# Integrator.net
KiCad netlist of a schematic drawn in Altium Designer
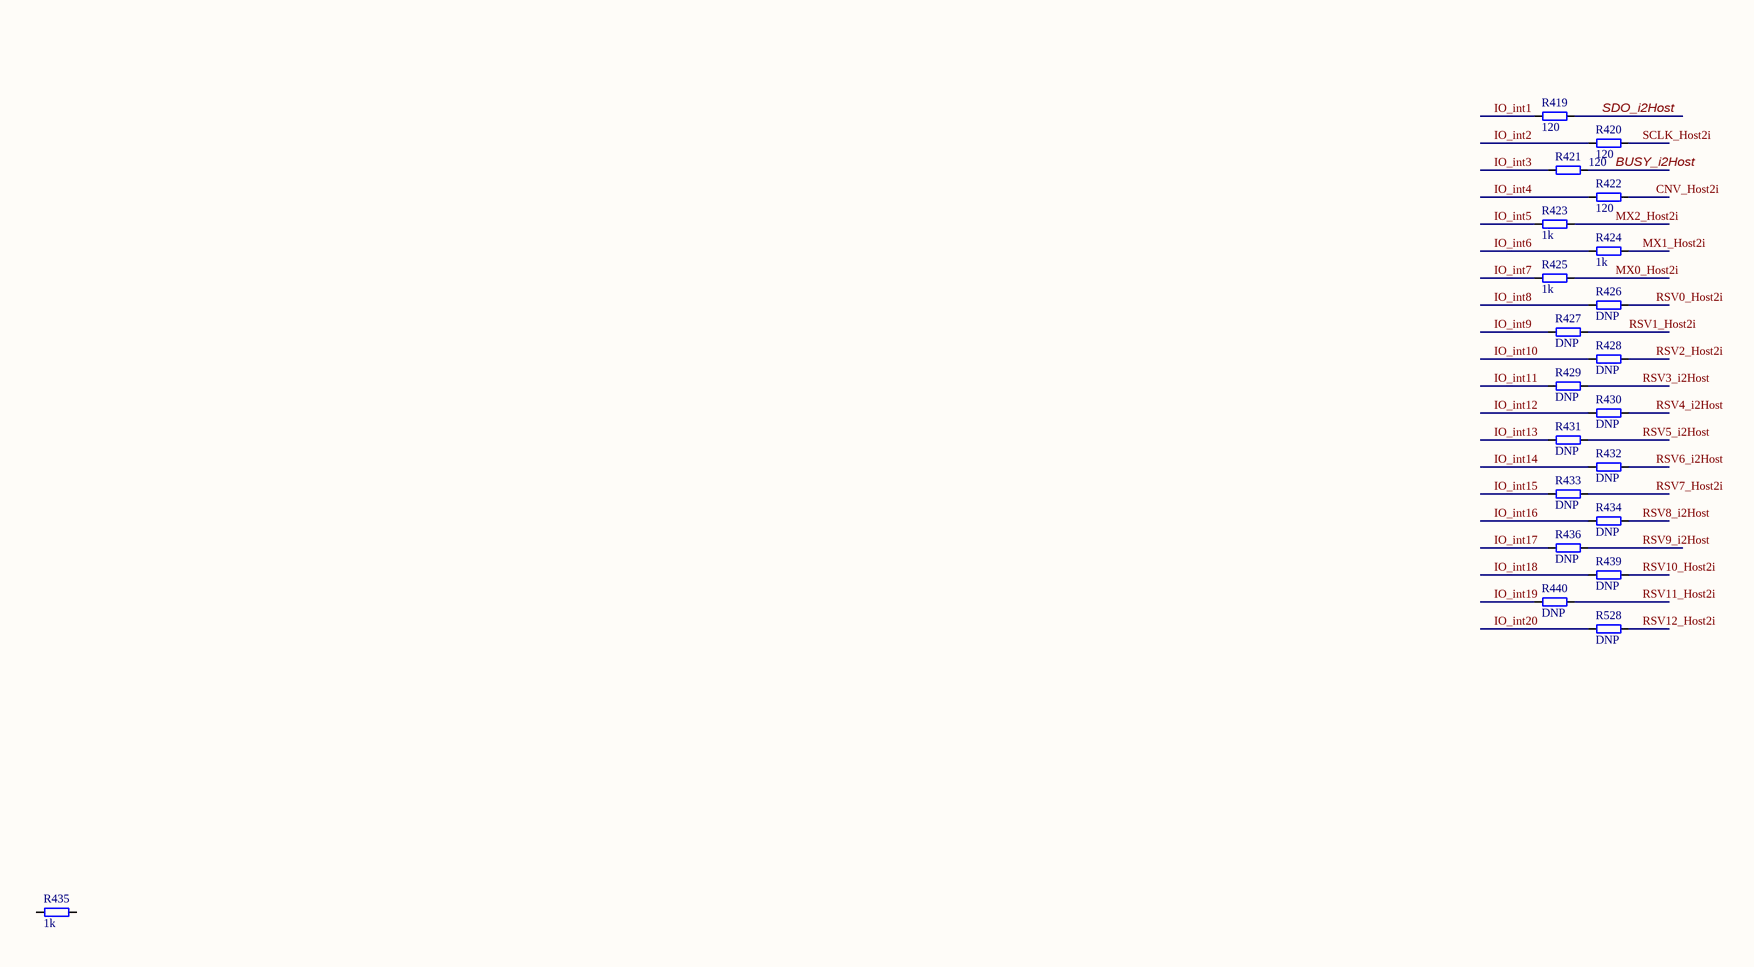
[diagram p0: Integrator.SchDoc, left]
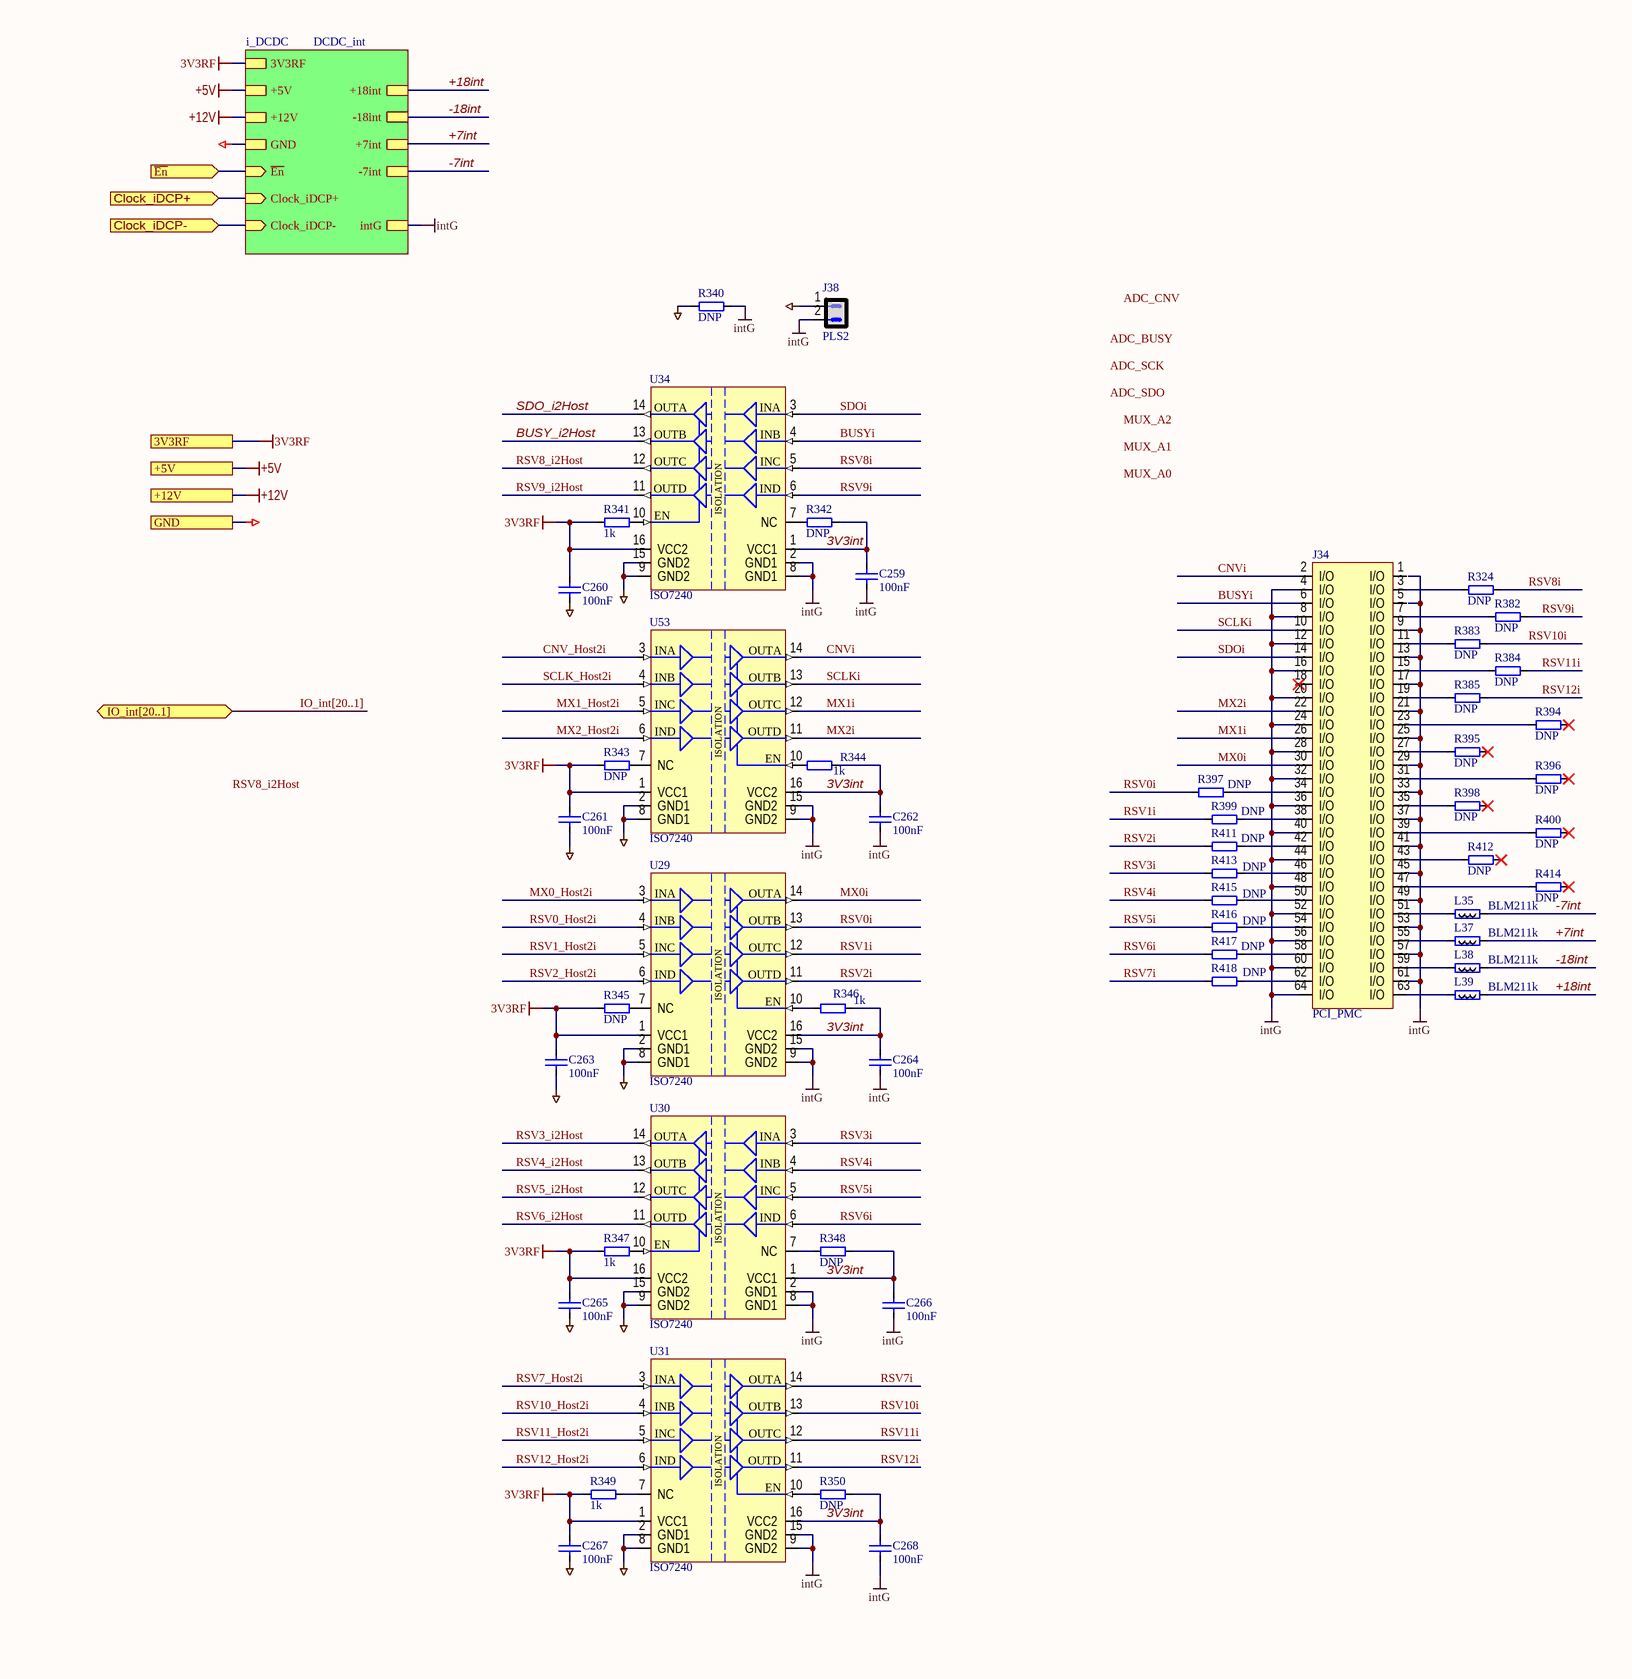
[diagram p1: Integrator.SchDoc, right]

(export (version "E")
  (design (tool "Eeschema 10.0.6"))
  (components
    (comp (ref "C259")
      (value "100nF")
      (footprint "SMD0805CAP")
      (description "Чип конденсатор 0805")
      (fields (field (name "VOLTAGE") "25V") (field (name "TOLERANCE") "20%"))
      (libsource (lib "DDSintLib") (part "C0805"))
    )
    (comp (ref "C260")
      (value "100nF")
      (footprint "SMD0805CAP")
      (description "Чип конденсатор 0805")
      (fields (field (name "VOLTAGE") "25V") (field (name "TOLERANCE") "20%"))
      (libsource (lib "DDSintLib") (part "C0805"))
    )
    (comp (ref "C261")
      (value "100nF")
      (footprint "SMD0805CAP")
      (description "Чип конденсатор 0805")
      (fields (field (name "VOLTAGE") "25V") (field (name "TOLERANCE") "20%"))
      (libsource (lib "DDSintLib") (part "C0805"))
    )
    (comp (ref "C262")
      (value "100nF")
      (footprint "SMD0805CAP")
      (description "Чип конденсатор 0805")
      (fields (field (name "VOLTAGE") "25V") (field (name "TOLERANCE") "20%"))
      (libsource (lib "DDSintLib") (part "C0805"))
    )
    (comp (ref "C263")
      (value "100nF")
      (footprint "SMD0805CAP")
      (description "Чип конденсатор 0805")
      (fields (field (name "VOLTAGE") "25V") (field (name "TOLERANCE") "20%"))
      (libsource (lib "DDSintLib") (part "C0805"))
    )
    (comp (ref "C264")
      (value "100nF")
      (footprint "SMD0805CAP")
      (description "Чип конденсатор 0805")
      (fields (field (name "VOLTAGE") "25V") (field (name "TOLERANCE") "20%"))
      (libsource (lib "DDSintLib") (part "C0805"))
    )
    (comp (ref "C265")
      (value "100nF")
      (footprint "SMD0805CAP")
      (description "Чип конденсатор 0805")
      (fields (field (name "VOLTAGE") "25V") (field (name "TOLERANCE") "20%"))
      (libsource (lib "DDSintLib") (part "C0805"))
    )
    (comp (ref "C266")
      (value "100nF")
      (footprint "SMD0805CAP")
      (description "Чип конденсатор 0805")
      (fields (field (name "VOLTAGE") "25V") (field (name "TOLERANCE") "20%"))
      (libsource (lib "DDSintLib") (part "C0805"))
    )
    (comp (ref "C267")
      (value "100nF")
      (footprint "SMD0805CAP")
      (description "Чип конденсатор 0805")
      (fields (field (name "VOLTAGE") "25V") (field (name "TOLERANCE") "20%"))
      (libsource (lib "DDSintLib") (part "C0805"))
    )
    (comp (ref "C268")
      (value "100nF")
      (footprint "SMD0805CAP")
      (description "Чип конденсатор 0805")
      (fields (field (name "VOLTAGE") "25V") (field (name "TOLERANCE") "20%"))
      (libsource (lib "DDSintLib") (part "C0805"))
    )
    (comp (ref "J34")
      (value "PCI_PMC")
      (footprint "TYCO_120521-1")
      (description "PCI Mezzanine Connector; IEEE 1386 MainBoard")
      (libsource (lib "DDSintLib") (part "PCI_PMC_M"))
    )
    (comp (ref "J38") (value "PLS2") (footprint "PLS2") (libsource (lib "DDSintLib") (part "PLS2")))
    (comp (ref "L35")
      (value "BLM211k")
      (footprint "RESC2012X50N")
      (description "SMD Ferrite bead 0805")
      (libsource (lib "DDSintLib") (part "BLM21"))
    )
    (comp (ref "L37")
      (value "BLM211k")
      (footprint "RESC2012X50N")
      (description "SMD Ferrite bead 0805")
      (libsource (lib "DDSintLib") (part "BLM21"))
    )
    (comp (ref "L38")
      (value "BLM211k")
      (footprint "RESC2012X50N")
      (description "SMD Ferrite bead 0805")
      (libsource (lib "DDSintLib") (part "BLM21"))
    )
    (comp (ref "L39")
      (value "BLM211k")
      (footprint "RESC2012X50N")
      (description "SMD Ferrite bead 0805")
      (libsource (lib "DDSintLib") (part "BLM21"))
    )
    (comp (ref "R324")
      (value "DNP")
      (footprint "SMD0805RES")
      (description "Чип резистор 0805")
      (fields (field (name "TOLERANCE") "1%"))
      (libsource (lib "DDSintLib") (part "R0805"))
    )
    (comp (ref "R340")
      (value "DNP")
      (footprint "SMD0805RES")
      (description "Чип резистор 0805")
      (fields (field (name "TOLERANCE") "1%"))
      (libsource (lib "DDSintLib") (part "R0805"))
    )
    (comp (ref "R341")
      (value "1k")
      (footprint "SMD0805RES")
      (description "Чип резистор 0805")
      (fields (field (name "TOLERANCE") "1%"))
      (libsource (lib "DDSintLib") (part "R0805"))
    )
    (comp (ref "R342")
      (value "DNP")
      (footprint "SMD0805RES")
      (description "Чип резистор 0805")
      (fields (field (name "TOLERANCE") "1%"))
      (libsource (lib "DDSintLib") (part "R0805"))
    )
    (comp (ref "R343")
      (value "DNP")
      (footprint "SMD0805RES")
      (description "Чип резистор 0805")
      (fields (field (name "TOLERANCE") "1%"))
      (libsource (lib "DDSintLib") (part "R0805"))
    )
    (comp (ref "R344")
      (value "1k")
      (footprint "SMD0805RES")
      (description "Чип резистор 0805")
      (fields (field (name "TOLERANCE") "1%"))
      (libsource (lib "DDSintLib") (part "R0805"))
    )
    (comp (ref "R345")
      (value "DNP")
      (footprint "SMD0805RES")
      (description "Чип резистор 0805")
      (fields (field (name "TOLERANCE") "1%"))
      (libsource (lib "DDSintLib") (part "R0805"))
    )
    (comp (ref "R346")
      (value "1k")
      (footprint "SMD0805RES")
      (description "Чип резистор 0805")
      (fields (field (name "TOLERANCE") "1%"))
      (libsource (lib "DDSintLib") (part "R0805"))
    )
    (comp (ref "R347")
      (value "1k")
      (footprint "SMD0805RES")
      (description "Чип резистор 0805")
      (fields (field (name "TOLERANCE") "1%"))
      (libsource (lib "DDSintLib") (part "R0805"))
    )
    (comp (ref "R348")
      (value "DNP")
      (footprint "SMD0805RES")
      (description "Чип резистор 0805")
      (fields (field (name "TOLERANCE") "1%"))
      (libsource (lib "DDSintLib") (part "R0805"))
    )
    (comp (ref "R349")
      (value "1k")
      (footprint "SMD0805RES")
      (description "Чип резистор 0805")
      (fields (field (name "TOLERANCE") "1%"))
      (libsource (lib "DDSintLib") (part "R0805"))
    )
    (comp (ref "R350")
      (value "DNP")
      (footprint "SMD0805RES")
      (description "Чип резистор 0805")
      (fields (field (name "TOLERANCE") "1%"))
      (libsource (lib "DDSintLib") (part "R0805"))
    )
    (comp (ref "R382")
      (value "DNP")
      (footprint "SMD0805RES")
      (description "Чип резистор 0805")
      (fields (field (name "TOLERANCE") "1%"))
      (libsource (lib "DDSintLib") (part "R0805"))
    )
    (comp (ref "R383")
      (value "DNP")
      (footprint "SMD0805RES")
      (description "Чип резистор 0805")
      (fields (field (name "TOLERANCE") "1%"))
      (libsource (lib "DDSintLib") (part "R0805"))
    )
    (comp (ref "R384")
      (value "DNP")
      (footprint "SMD0805RES")
      (description "Чип резистор 0805")
      (fields (field (name "TOLERANCE") "1%"))
      (libsource (lib "DDSintLib") (part "R0805"))
    )
    (comp (ref "R385")
      (value "DNP")
      (footprint "SMD0805RES")
      (description "Чип резистор 0805")
      (fields (field (name "TOLERANCE") "1%"))
      (libsource (lib "DDSintLib") (part "R0805"))
    )
    (comp (ref "R394")
      (value "DNP")
      (footprint "SMD0805RES")
      (description "Чип резистор 0805")
      (fields (field (name "TOLERANCE") "1%"))
      (libsource (lib "DDSintLib") (part "R0805"))
    )
    (comp (ref "R395")
      (value "DNP")
      (footprint "SMD0805RES")
      (description "Чип резистор 0805")
      (fields (field (name "TOLERANCE") "1%"))
      (libsource (lib "DDSintLib") (part "R0805"))
    )
    (comp (ref "R396")
      (value "DNP")
      (footprint "SMD0805RES")
      (description "Чип резистор 0805")
      (fields (field (name "TOLERANCE") "1%"))
      (libsource (lib "DDSintLib") (part "R0805"))
    )
    (comp (ref "R397")
      (value "DNP")
      (footprint "SMD0805RES")
      (description "Чип резистор 0805")
      (fields (field (name "TOLERANCE") "1%"))
      (libsource (lib "DDSintLib") (part "R0805"))
    )
    (comp (ref "R398")
      (value "DNP")
      (footprint "SMD0805RES")
      (description "Чип резистор 0805")
      (fields (field (name "TOLERANCE") "1%"))
      (libsource (lib "DDSintLib") (part "R0805"))
    )
    (comp (ref "R399")
      (value "DNP")
      (footprint "SMD0805RES")
      (description "Чип резистор 0805")
      (fields (field (name "TOLERANCE") "1%"))
      (libsource (lib "DDSintLib") (part "R0805"))
    )
    (comp (ref "R400")
      (value "DNP")
      (footprint "SMD0805RES")
      (description "Чип резистор 0805")
      (fields (field (name "TOLERANCE") "1%"))
      (libsource (lib "DDSintLib") (part "R0805"))
    )
    (comp (ref "R411")
      (value "DNP")
      (footprint "SMD0805RES")
      (description "Чип резистор 0805")
      (fields (field (name "TOLERANCE") "1%"))
      (libsource (lib "DDSintLib") (part "R0805"))
    )
    (comp (ref "R412")
      (value "DNP")
      (footprint "SMD0805RES")
      (description "Чип резистор 0805")
      (fields (field (name "TOLERANCE") "1%"))
      (libsource (lib "DDSintLib") (part "R0805"))
    )
    (comp (ref "R413")
      (value "DNP")
      (footprint "SMD0805RES")
      (description "Чип резистор 0805")
      (fields (field (name "TOLERANCE") "1%"))
      (libsource (lib "DDSintLib") (part "R0805"))
    )
    (comp (ref "R414")
      (value "DNP")
      (footprint "SMD0805RES")
      (description "Чип резистор 0805")
      (fields (field (name "TOLERANCE") "1%"))
      (libsource (lib "DDSintLib") (part "R0805"))
    )
    (comp (ref "R415")
      (value "DNP")
      (footprint "SMD0805RES")
      (description "Чип резистор 0805")
      (fields (field (name "TOLERANCE") "1%"))
      (libsource (lib "DDSintLib") (part "R0805"))
    )
    (comp (ref "R416")
      (value "DNP")
      (footprint "SMD0805RES")
      (description "Чип резистор 0805")
      (fields (field (name "TOLERANCE") "1%"))
      (libsource (lib "DDSintLib") (part "R0805"))
    )
    (comp (ref "R417")
      (value "DNP")
      (footprint "SMD0805RES")
      (description "Чип резистор 0805")
      (fields (field (name "TOLERANCE") "1%"))
      (libsource (lib "DDSintLib") (part "R0805"))
    )
    (comp (ref "R418")
      (value "DNP")
      (footprint "SMD0805RES")
      (description "Чип резистор 0805")
      (fields (field (name "TOLERANCE") "1%"))
      (libsource (lib "DDSintLib") (part "R0805"))
    )
    (comp (ref "R419")
      (value "120")
      (footprint "SMD0805RES")
      (description "Чип резистор 0805")
      (fields (field (name "TOLERANCE") "1%"))
      (libsource (lib "DDSintLib") (part "R0805"))
    )
    (comp (ref "R420")
      (value "120")
      (footprint "SMD0805RES")
      (description "Чип резистор 0805")
      (fields (field (name "TOLERANCE") "1%"))
      (libsource (lib "DDSintLib") (part "R0805"))
    )
    (comp (ref "R421")
      (value "120")
      (footprint "SMD0805RES")
      (description "Чип резистор 0805")
      (fields (field (name "TOLERANCE") "1%"))
      (libsource (lib "DDSintLib") (part "R0805"))
    )
    (comp (ref "R422")
      (value "120")
      (footprint "SMD0805RES")
      (description "Чип резистор 0805")
      (fields (field (name "TOLERANCE") "1%"))
      (libsource (lib "DDSintLib") (part "R0805"))
    )
    (comp (ref "R423")
      (value "1k")
      (footprint "SMD0805RES")
      (description "Чип резистор 0805")
      (fields (field (name "TOLERANCE") "1%"))
      (libsource (lib "DDSintLib") (part "R0805"))
    )
    (comp (ref "R424")
      (value "1k")
      (footprint "SMD0805RES")
      (description "Чип резистор 0805")
      (fields (field (name "TOLERANCE") "1%"))
      (libsource (lib "DDSintLib") (part "R0805"))
    )
    (comp (ref "R425")
      (value "1k")
      (footprint "SMD0805RES")
      (description "Чип резистор 0805")
      (fields (field (name "TOLERANCE") "1%"))
      (libsource (lib "DDSintLib") (part "R0805"))
    )
    (comp (ref "R426")
      (value "DNP")
      (footprint "SMD0805RES")
      (description "Чип резистор 0805")
      (fields (field (name "TOLERANCE") "1%"))
      (libsource (lib "DDSintLib") (part "R0805"))
    )
    (comp (ref "R427")
      (value "DNP")
      (footprint "SMD0805RES")
      (description "Чип резистор 0805")
      (fields (field (name "TOLERANCE") "1%"))
      (libsource (lib "DDSintLib") (part "R0805"))
    )
    (comp (ref "R428")
      (value "DNP")
      (footprint "SMD0805RES")
      (description "Чип резистор 0805")
      (fields (field (name "TOLERANCE") "1%"))
      (libsource (lib "DDSintLib") (part "R0805"))
    )
    (comp (ref "R429")
      (value "DNP")
      (footprint "SMD0805RES")
      (description "Чип резистор 0805")
      (fields (field (name "TOLERANCE") "1%"))
      (libsource (lib "DDSintLib") (part "R0805"))
    )
    (comp (ref "R430")
      (value "DNP")
      (footprint "SMD0805RES")
      (description "Чип резистор 0805")
      (fields (field (name "TOLERANCE") "1%"))
      (libsource (lib "DDSintLib") (part "R0805"))
    )
    (comp (ref "R431")
      (value "DNP")
      (footprint "SMD0805RES")
      (description "Чип резистор 0805")
      (fields (field (name "TOLERANCE") "1%"))
      (libsource (lib "DDSintLib") (part "R0805"))
    )
    (comp (ref "R432")
      (value "DNP")
      (footprint "SMD0805RES")
      (description "Чип резистор 0805")
      (fields (field (name "TOLERANCE") "1%"))
      (libsource (lib "DDSintLib") (part "R0805"))
    )
    (comp (ref "R433")
      (value "DNP")
      (footprint "SMD0805RES")
      (description "Чип резистор 0805")
      (fields (field (name "TOLERANCE") "1%"))
      (libsource (lib "DDSintLib") (part "R0805"))
    )
    (comp (ref "R434")
      (value "DNP")
      (footprint "SMD0805RES")
      (description "Чип резистор 0805")
      (fields (field (name "TOLERANCE") "1%"))
      (libsource (lib "DDSintLib") (part "R0805"))
    )
    (comp (ref "R435")
      (value "1k")
      (footprint "SMD0805RES")
      (description "Чип резистор 0805")
      (fields (field (name "TOLERANCE") "1%"))
      (libsource (lib "DDSintLib") (part "R0805"))
    )
    (comp (ref "R436")
      (value "DNP")
      (footprint "SMD0805RES")
      (description "Чип резистор 0805")
      (fields (field (name "TOLERANCE") "1%"))
      (libsource (lib "DDSintLib") (part "R0805"))
    )
    (comp (ref "R439")
      (value "DNP")
      (footprint "SMD0805RES")
      (description "Чип резистор 0805")
      (fields (field (name "TOLERANCE") "1%"))
      (libsource (lib "DDSintLib") (part "R0805"))
    )
    (comp (ref "R440")
      (value "DNP")
      (footprint "SMD0805RES")
      (description "Чип резистор 0805")
      (fields (field (name "TOLERANCE") "1%"))
      (libsource (lib "DDSintLib") (part "R0805"))
    )
    (comp (ref "R528")
      (value "DNP")
      (footprint "SMD0805RES")
      (description "Чип резистор 0805")
      (fields (field (name "TOLERANCE") "1%"))
      (libsource (lib "DDSintLib") (part "R0805"))
    )
    (comp (ref "U29")
      (value "ISO7240")
      (footprint "SOIC127P1030X265-16N")
      (description "Двунаправленный буфер")
      (fields (field (name "VOLTAGE") "3V3 or 5V"))
      (libsource (lib "DDSintLib") (part "ISO7240M"))
    )
    (comp (ref "U30")
      (value "ISO7240")
      (footprint "SOIC127P1030X265-16N")
      (description "Двунаправленный буфер")
      (fields (field (name "VOLTAGE") "3V3 or 5V"))
      (libsource (lib "DDSintLib") (part "ISO7240M"))
    )
    (comp (ref "U31")
      (value "ISO7240")
      (footprint "SOIC127P1030X265-16N")
      (description "Двунаправленный буфер")
      (fields (field (name "VOLTAGE") "3V3 or 5V"))
      (libsource (lib "DDSintLib") (part "ISO7240M"))
    )
    (comp (ref "U34")
      (value "ISO7240")
      (footprint "SOIC127P1030X265-16N")
      (description "Двунаправленный буфер")
      (fields (field (name "VOLTAGE") "3V3 or 5V"))
      (libsource (lib "DDSintLib") (part "ISO7240M"))
    )
    (comp (ref "U53")
      (value "ISO7240")
      (footprint "SOIC127P1030X265-16N")
      (description "Двунаправленный буфер")
      (fields (field (name "VOLTAGE") "3V3 or 5V"))
      (libsource (lib "DDSintLib") (part "ISO7240M"))
    )
  )
  (nets
    (net (code "3") (name "/+7int") (class "Default")
      (node (ref "L37") (pin "2") (pinfunction "2_2") (pintype "passive"))
    )
    (net (code "4") (name "/+18int") (class "Default")
      (node (ref "L39") (pin "2") (pinfunction "2_2") (pintype "passive"))
    )
    (net (code "5") (name "/-7int") (class "Default")
      (node (ref "L35") (pin "2") (pinfunction "2_2") (pintype "passive"))
    )
    (net (code "6") (name "/-18int") (class "Default")
      (node (ref "L38") (pin "2") (pinfunction "2_2") (pintype "passive"))
    )
    (net (code "7") (name "/3V3int") (class "Default")
      (node (ref "C259") (pin "2") (pinfunction "2_2") (pintype "passive"))
      (node (ref "C262") (pin "2") (pinfunction "2_2") (pintype "passive"))
      (node (ref "C264") (pin "2") (pinfunction "2_2") (pintype "passive"))
      (node (ref "C266") (pin "2") (pinfunction "2_2") (pintype "passive"))
      (node (ref "C268") (pin "2") (pinfunction "2_2") (pintype "passive"))
      (node (ref "R342") (pin "2") (pinfunction "2_2") (pintype "passive"))
      (node (ref "R344") (pin "2") (pinfunction "2_2") (pintype "passive"))
      (node (ref "R346") (pin "2") (pinfunction "2_2") (pintype "passive"))
      (node (ref "R348") (pin "2") (pinfunction "2_2") (pintype "passive"))
      (node (ref "R350") (pin "2") (pinfunction "2_2") (pintype "passive"))
      (node (ref "U29") (pin "16") (pinfunction "VCC2_16") (pintype "power_in"))
      (node (ref "U30") (pin "1") (pinfunction "VCC1_1") (pintype "power_in"))
      (node (ref "U31") (pin "16") (pinfunction "VCC2_16") (pintype "power_in"))
      (node (ref "U34") (pin "1") (pinfunction "VCC1_1") (pintype "power_in"))
      (node (ref "U53") (pin "16") (pinfunction "VCC2_16") (pintype "power_in"))
    )
    (net (code "12") (name "/BUSY_i2Host") (class "Default")
      (node (ref "R421") (pin "2") (pinfunction "2_2") (pintype "passive"))
      (node (ref "U34") (pin "13") (pinfunction "OUTB_13") (pintype "output"))
    )
    (net (code "13") (name "/BUSYi") (class "Default")
      (node (ref "J34") (pin "6") (pinfunction "I/O_6") (pintype "bidirectional"))
      (node (ref "U34") (pin "4") (pinfunction "INB_4") (pintype "input"))
    )
    (net (code "14") (name "/CNV_Host2i") (class "Default")
      (node (ref "R422") (pin "2") (pinfunction "2_2") (pintype "passive"))
      (node (ref "U53") (pin "3") (pinfunction "INA_3") (pintype "input"))
    )
    (net (code "15") (name "/CNVi") (class "Default")
      (node (ref "J34") (pin "2") (pinfunction "I/O_2") (pintype "bidirectional"))
      (node (ref "U53") (pin "14") (pinfunction "OUTA_14") (pintype "output"))
    )
    (net (code "19") (name "/IO_int1") (class "Default")
      (node (ref "R419") (pin "1") (pinfunction "1_1") (pintype "passive"))
    )
    (net (code "20") (name "/IO_int2") (class "Default")
      (node (ref "R420") (pin "1") (pinfunction "1_1") (pintype "passive"))
    )
    (net (code "21") (name "/IO_int3") (class "Default")
      (node (ref "R421") (pin "1") (pinfunction "1_1") (pintype "passive"))
    )
    (net (code "22") (name "/IO_int4") (class "Default")
      (node (ref "R422") (pin "1") (pinfunction "1_1") (pintype "passive"))
    )
    (net (code "23") (name "/IO_int5") (class "Default")
      (node (ref "R423") (pin "1") (pinfunction "1_1") (pintype "passive"))
    )
    (net (code "24") (name "/IO_int6") (class "Default")
      (node (ref "R424") (pin "1") (pinfunction "1_1") (pintype "passive"))
    )
    (net (code "25") (name "/IO_int7") (class "Default")
      (node (ref "R425") (pin "1") (pinfunction "1_1") (pintype "passive"))
    )
    (net (code "26") (name "/IO_int8") (class "Default")
      (node (ref "R426") (pin "1") (pinfunction "1_1") (pintype "passive"))
    )
    (net (code "27") (name "/IO_int9") (class "Default")
      (node (ref "R427") (pin "1") (pinfunction "1_1") (pintype "passive"))
    )
    (net (code "28") (name "/IO_int10") (class "Default")
      (node (ref "R428") (pin "1") (pinfunction "1_1") (pintype "passive"))
    )
    (net (code "29") (name "/IO_int11") (class "Default")
      (node (ref "R429") (pin "1") (pinfunction "1_1") (pintype "passive"))
    )
    (net (code "30") (name "/IO_int12") (class "Default")
      (node (ref "R430") (pin "1") (pinfunction "1_1") (pintype "passive"))
    )
    (net (code "31") (name "/IO_int13") (class "Default")
      (node (ref "R431") (pin "1") (pinfunction "1_1") (pintype "passive"))
    )
    (net (code "32") (name "/IO_int14") (class "Default")
      (node (ref "R432") (pin "1") (pinfunction "1_1") (pintype "passive"))
    )
    (net (code "33") (name "/IO_int15") (class "Default")
      (node (ref "R433") (pin "1") (pinfunction "1_1") (pintype "passive"))
    )
    (net (code "34") (name "/IO_int16") (class "Default")
      (node (ref "R434") (pin "1") (pinfunction "1_1") (pintype "passive"))
    )
    (net (code "35") (name "/IO_int17") (class "Default")
      (node (ref "R436") (pin "1") (pinfunction "1_1") (pintype "passive"))
    )
    (net (code "36") (name "/IO_int18") (class "Default")
      (node (ref "R439") (pin "1") (pinfunction "1_1") (pintype "passive"))
    )
    (net (code "37") (name "/IO_int19") (class "Default")
      (node (ref "R440") (pin "1") (pinfunction "1_1") (pintype "passive"))
    )
    (net (code "38") (name "/IO_int20") (class "Default")
      (node (ref "R528") (pin "1") (pinfunction "1_1") (pintype "passive"))
    )
    (net (code "43") (name "/MX0_Host2i") (class "Default")
      (node (ref "R425") (pin "2") (pinfunction "2_2") (pintype "passive"))
      (node (ref "U29") (pin "3") (pinfunction "INA_3") (pintype "input"))
    )
    (net (code "44") (name "/MX0i") (class "Default")
      (node (ref "J34") (pin "30") (pinfunction "I/O_30") (pintype "bidirectional"))
      (node (ref "U29") (pin "14") (pinfunction "OUTA_14") (pintype "output"))
    )
    (net (code "45") (name "/MX1_Host2i") (class "Default")
      (node (ref "R424") (pin "2") (pinfunction "2_2") (pintype "passive"))
      (node (ref "U53") (pin "5") (pinfunction "INC_5") (pintype "input"))
    )
    (net (code "46") (name "/MX1i") (class "Default")
      (node (ref "J34") (pin "26") (pinfunction "I/O_26") (pintype "bidirectional"))
      (node (ref "U53") (pin "12") (pinfunction "OUTC_12") (pintype "output"))
    )
    (net (code "47") (name "/MX2_Host2i") (class "Default")
      (node (ref "R423") (pin "2") (pinfunction "2_2") (pintype "passive"))
      (node (ref "U53") (pin "6") (pinfunction "IND_6") (pintype "input"))
    )
    (net (code "48") (name "/MX2i") (class "Default")
      (node (ref "J34") (pin "22") (pinfunction "I/O_22") (pintype "bidirectional"))
      (node (ref "U53") (pin "11") (pinfunction "OUTD_11") (pintype "output"))
    )
    (net (code "49") (name "/RSV0_Host2i") (class "Default")
      (node (ref "R426") (pin "2") (pinfunction "2_2") (pintype "passive"))
      (node (ref "U29") (pin "4") (pinfunction "INB_4") (pintype "input"))
    )
    (net (code "50") (name "/RSV0i") (class "Default")
      (node (ref "R397") (pin "1") (pinfunction "1_1") (pintype "passive"))
      (node (ref "U29") (pin "13") (pinfunction "OUTB_13") (pintype "output"))
    )
    (net (code "51") (name "/RSV1_Host2i") (class "Default")
      (node (ref "R427") (pin "2") (pinfunction "2_2") (pintype "passive"))
      (node (ref "U29") (pin "5") (pinfunction "INC_5") (pintype "input"))
    )
    (net (code "52") (name "/RSV1i") (class "Default")
      (node (ref "R399") (pin "1") (pinfunction "1_1") (pintype "passive"))
      (node (ref "U29") (pin "12") (pinfunction "OUTC_12") (pintype "output"))
    )
    (net (code "53") (name "/RSV2_Host2i") (class "Default")
      (node (ref "R428") (pin "2") (pinfunction "2_2") (pintype "passive"))
      (node (ref "U29") (pin "6") (pinfunction "IND_6") (pintype "input"))
    )
    (net (code "54") (name "/RSV2i") (class "Default")
      (node (ref "R411") (pin "1") (pinfunction "1_1") (pintype "passive"))
      (node (ref "U29") (pin "11") (pinfunction "OUTD_11") (pintype "output"))
    )
    (net (code "55") (name "/RSV3_i2Host") (class "Default")
      (node (ref "R429") (pin "2") (pinfunction "2_2") (pintype "passive"))
      (node (ref "U30") (pin "14") (pinfunction "OUTA_14") (pintype "output"))
    )
    (net (code "56") (name "/RSV3i") (class "Default")
      (node (ref "R413") (pin "1") (pinfunction "1_1") (pintype "passive"))
      (node (ref "U30") (pin "3") (pinfunction "INA_3") (pintype "input"))
    )
    (net (code "57") (name "/RSV4_i2Host") (class "Default")
      (node (ref "R430") (pin "2") (pinfunction "2_2") (pintype "passive"))
      (node (ref "U30") (pin "13") (pinfunction "OUTB_13") (pintype "output"))
    )
    (net (code "58") (name "/RSV4i") (class "Default")
      (node (ref "R415") (pin "1") (pinfunction "1_1") (pintype "passive"))
      (node (ref "U30") (pin "4") (pinfunction "INB_4") (pintype "input"))
    )
    (net (code "59") (name "/RSV5_i2Host") (class "Default")
      (node (ref "R431") (pin "2") (pinfunction "2_2") (pintype "passive"))
      (node (ref "U30") (pin "12") (pinfunction "OUTC_12") (pintype "output"))
    )
    (net (code "60") (name "/RSV5i") (class "Default")
      (node (ref "R416") (pin "1") (pinfunction "1_1") (pintype "passive"))
      (node (ref "U30") (pin "5") (pinfunction "INC_5") (pintype "input"))
    )
    (net (code "61") (name "/RSV6_i2Host") (class "Default")
      (node (ref "R432") (pin "2") (pinfunction "2_2") (pintype "passive"))
      (node (ref "U30") (pin "11") (pinfunction "OUTD_11") (pintype "output"))
    )
    (net (code "62") (name "/RSV6i") (class "Default")
      (node (ref "R417") (pin "1") (pinfunction "1_1") (pintype "passive"))
      (node (ref "U30") (pin "6") (pinfunction "IND_6") (pintype "input"))
    )
    (net (code "63") (name "/RSV7_Host2i") (class "Default")
      (node (ref "R433") (pin "2") (pinfunction "2_2") (pintype "passive"))
      (node (ref "U31") (pin "3") (pinfunction "INA_3") (pintype "input"))
    )
    (net (code "64") (name "/RSV7i") (class "Default")
      (node (ref "R418") (pin "1") (pinfunction "1_1") (pintype "passive"))
      (node (ref "U31") (pin "14") (pinfunction "OUTA_14") (pintype "output"))
    )
    (net (code "65") (name "/RSV8_i2Host") (class "Default")
      (node (ref "R434") (pin "2") (pinfunction "2_2") (pintype "passive"))
      (node (ref "U34") (pin "12") (pinfunction "OUTC_12") (pintype "output"))
    )
    (net (code "66") (name "/RSV8i") (class "Default")
      (node (ref "R324") (pin "2") (pinfunction "2_2") (pintype "passive"))
      (node (ref "U34") (pin "5") (pinfunction "INC_5") (pintype "input"))
    )
    (net (code "67") (name "/RSV9_i2Host") (class "Default")
      (node (ref "R436") (pin "2") (pinfunction "2_2") (pintype "passive"))
      (node (ref "U34") (pin "11") (pinfunction "OUTD_11") (pintype "output"))
    )
    (net (code "68") (name "/RSV9i") (class "Default")
      (node (ref "R382") (pin "2") (pinfunction "2_2") (pintype "passive"))
      (node (ref "U34") (pin "6") (pinfunction "IND_6") (pintype "input"))
    )
    (net (code "69") (name "/RSV10_Host2i") (class "Default")
      (node (ref "R439") (pin "2") (pinfunction "2_2") (pintype "passive"))
      (node (ref "U31") (pin "4") (pinfunction "INB_4") (pintype "input"))
    )
    (net (code "70") (name "/RSV10i") (class "Default")
      (node (ref "R383") (pin "2") (pinfunction "2_2") (pintype "passive"))
      (node (ref "U31") (pin "13") (pinfunction "OUTB_13") (pintype "output"))
    )
    (net (code "71") (name "/RSV11_Host2i") (class "Default")
      (node (ref "R440") (pin "2") (pinfunction "2_2") (pintype "passive"))
      (node (ref "U31") (pin "5") (pinfunction "INC_5") (pintype "input"))
    )
    (net (code "72") (name "/RSV11i") (class "Default")
      (node (ref "R384") (pin "2") (pinfunction "2_2") (pintype "passive"))
      (node (ref "U31") (pin "12") (pinfunction "OUTC_12") (pintype "output"))
    )
    (net (code "73") (name "/RSV12_Host2i") (class "Default")
      (node (ref "R528") (pin "2") (pinfunction "2_2") (pintype "passive"))
      (node (ref "U31") (pin "6") (pinfunction "IND_6") (pintype "input"))
    )
    (net (code "74") (name "/RSV12i") (class "Default")
      (node (ref "R385") (pin "2") (pinfunction "2_2") (pintype "passive"))
      (node (ref "U31") (pin "11") (pinfunction "OUTD_11") (pintype "output"))
    )
    (net (code "75") (name "/SCLK_Host2i") (class "Default")
      (node (ref "R420") (pin "2") (pinfunction "2_2") (pintype "passive"))
      (node (ref "U53") (pin "4") (pinfunction "INB_4") (pintype "input"))
    )
    (net (code "76") (name "/SCLKi") (class "Default")
      (node (ref "J34") (pin "10") (pinfunction "I/O_10") (pintype "bidirectional"))
      (node (ref "U53") (pin "13") (pinfunction "OUTB_13") (pintype "output"))
    )
    (net (code "77") (name "/SDO_i2Host") (class "Default")
      (node (ref "R419") (pin "2") (pinfunction "2_2") (pintype "passive"))
      (node (ref "U34") (pin "14") (pinfunction "OUTA_14") (pintype "output"))
    )
    (net (code "78") (name "/SDOi") (class "Default")
      (node (ref "J34") (pin "14") (pinfunction "I/O_14") (pintype "bidirectional"))
      (node (ref "U34") (pin "3") (pinfunction "INA_3") (pintype "input"))
    )
    (net (code "79") (name "3V3RF") (class "Default")
      (node (ref "C260") (pin "2") (pinfunction "2_2") (pintype "passive"))
      (node (ref "C261") (pin "2") (pinfunction "2_2") (pintype "passive"))
      (node (ref "C263") (pin "2") (pinfunction "2_2") (pintype "passive"))
      (node (ref "C265") (pin "2") (pinfunction "2_2") (pintype "passive"))
      (node (ref "C267") (pin "2") (pinfunction "2_2") (pintype "passive"))
      (node (ref "R341") (pin "1") (pinfunction "1_1") (pintype "passive"))
      (node (ref "R343") (pin "1") (pinfunction "1_1") (pintype "passive"))
      (node (ref "R345") (pin "1") (pinfunction "1_1") (pintype "passive"))
      (node (ref "R347") (pin "1") (pinfunction "1_1") (pintype "passive"))
      (node (ref "R349") (pin "1") (pinfunction "1_1") (pintype "passive"))
      (node (ref "U29") (pin "1") (pinfunction "VCC1_1") (pintype "power_in"))
      (node (ref "U30") (pin "16") (pinfunction "VCC2_16") (pintype "power_in"))
      (node (ref "U31") (pin "1") (pinfunction "VCC1_1") (pintype "power_in"))
      (node (ref "U34") (pin "16") (pinfunction "VCC2_16") (pintype "power_in"))
      (node (ref "U53") (pin "1") (pinfunction "VCC1_1") (pintype "power_in"))
    )
    (net (code "80") (name "GND") (class "Default")
      (node (ref "C260") (pin "1") (pinfunction "1_1") (pintype "passive"))
      (node (ref "C261") (pin "1") (pinfunction "1_1") (pintype "passive"))
      (node (ref "C263") (pin "1") (pinfunction "1_1") (pintype "passive"))
      (node (ref "C265") (pin "1") (pinfunction "1_1") (pintype "passive"))
      (node (ref "C267") (pin "1") (pinfunction "1_1") (pintype "passive"))
      (node (ref "J38") (pin "1") (pinfunction "1_1") (pintype "bidirectional"))
      (node (ref "R340") (pin "1") (pinfunction "1_1") (pintype "passive"))
      (node (ref "U29") (pin "2") (pinfunction "GND1_2") (pintype "power_in"))
      (node (ref "U29") (pin "8") (pinfunction "GND1_8") (pintype "power_in"))
      (node (ref "U30") (pin "15") (pinfunction "GND2_15") (pintype "power_in"))
      (node (ref "U30") (pin "9") (pinfunction "GND2_9") (pintype "power_in"))
      (node (ref "U31") (pin "2") (pinfunction "GND1_2") (pintype "power_in"))
      (node (ref "U31") (pin "8") (pinfunction "GND1_8") (pintype "power_in"))
      (node (ref "U34") (pin "15") (pinfunction "GND2_15") (pintype "power_in"))
      (node (ref "U34") (pin "9") (pinfunction "GND2_9") (pintype "power_in"))
      (node (ref "U53") (pin "2") (pinfunction "GND1_2") (pintype "power_in"))
      (node (ref "U53") (pin "8") (pinfunction "GND1_8") (pintype "power_in"))
    )
    (net (code "81") (name "Net-(J34-I{slash}O-Pad3)") (class "Default")
      (node (ref "J34") (pin "3") (pinfunction "I/O_3") (pintype "bidirectional"))
      (node (ref "R324") (pin "1") (pinfunction "1_1") (pintype "passive"))
    )
    (net (code "82") (name "Net-(J34-I{slash}O-Pad7)") (class "Default")
      (node (ref "J34") (pin "7") (pinfunction "I/O_7") (pintype "bidirectional"))
      (node (ref "R382") (pin "1") (pinfunction "1_1") (pintype "passive"))
    )
    (net (code "83") (name "Net-(J34-I{slash}O-Pad11)") (class "Default")
      (node (ref "J34") (pin "11") (pinfunction "I/O_11") (pintype "bidirectional"))
      (node (ref "R383") (pin "1") (pinfunction "1_1") (pintype "passive"))
    )
    (net (code "84") (name "Net-(J34-I{slash}O-Pad15)") (class "Default")
      (node (ref "J34") (pin "15") (pinfunction "I/O_15") (pintype "bidirectional"))
      (node (ref "R384") (pin "1") (pinfunction "1_1") (pintype "passive"))
    )
    (net (code "85") (name "Net-(J34-I{slash}O-Pad19)") (class "Default")
      (node (ref "J34") (pin "19") (pinfunction "I/O_19") (pintype "bidirectional"))
      (node (ref "R385") (pin "1") (pinfunction "1_1") (pintype "passive"))
    )
    (net (code "86") (name "Net-(J34-I{slash}O-Pad23)") (class "Default")
      (node (ref "J34") (pin "23") (pinfunction "I/O_23") (pintype "bidirectional"))
      (node (ref "R394") (pin "1") (pinfunction "1_1") (pintype "passive"))
    )
    (net (code "87") (name "Net-(J34-I{slash}O-Pad27)") (class "Default")
      (node (ref "J34") (pin "27") (pinfunction "I/O_27") (pintype "bidirectional"))
      (node (ref "R395") (pin "1") (pinfunction "1_1") (pintype "passive"))
    )
    (net (code "88") (name "Net-(J34-I{slash}O-Pad31)") (class "Default")
      (node (ref "J34") (pin "31") (pinfunction "I/O_31") (pintype "bidirectional"))
      (node (ref "R396") (pin "1") (pinfunction "1_1") (pintype "passive"))
    )
    (net (code "89") (name "Net-(J34-I{slash}O-Pad34)") (class "Default")
      (node (ref "J34") (pin "34") (pinfunction "I/O_34") (pintype "bidirectional"))
      (node (ref "R397") (pin "2") (pinfunction "2_2") (pintype "passive"))
    )
    (net (code "90") (name "Net-(J34-I{slash}O-Pad35)") (class "Default")
      (node (ref "J34") (pin "35") (pinfunction "I/O_35") (pintype "bidirectional"))
      (node (ref "R398") (pin "1") (pinfunction "1_1") (pintype "passive"))
    )
    (net (code "91") (name "Net-(J34-I{slash}O-Pad38)") (class "Default")
      (node (ref "J34") (pin "38") (pinfunction "I/O_38") (pintype "bidirectional"))
      (node (ref "R399") (pin "2") (pinfunction "2_2") (pintype "passive"))
    )
    (net (code "92") (name "Net-(J34-I{slash}O-Pad39)") (class "Default")
      (node (ref "J34") (pin "39") (pinfunction "I/O_39") (pintype "bidirectional"))
      (node (ref "R400") (pin "1") (pinfunction "1_1") (pintype "passive"))
    )
    (net (code "93") (name "Net-(J34-I{slash}O-Pad42)") (class "Default")
      (node (ref "J34") (pin "42") (pinfunction "I/O_42") (pintype "bidirectional"))
      (node (ref "R411") (pin "2") (pinfunction "2_2") (pintype "passive"))
    )
    (net (code "94") (name "Net-(J34-I{slash}O-Pad43)") (class "Default")
      (node (ref "J34") (pin "43") (pinfunction "I/O_43") (pintype "bidirectional"))
      (node (ref "R412") (pin "1") (pinfunction "1_1") (pintype "passive"))
    )
    (net (code "95") (name "Net-(J34-I{slash}O-Pad46)") (class "Default")
      (node (ref "J34") (pin "46") (pinfunction "I/O_46") (pintype "bidirectional"))
      (node (ref "R413") (pin "2") (pinfunction "2_2") (pintype "passive"))
    )
    (net (code "96") (name "Net-(J34-I{slash}O-Pad47)") (class "Default")
      (node (ref "J34") (pin "47") (pinfunction "I/O_47") (pintype "bidirectional"))
      (node (ref "R414") (pin "1") (pinfunction "1_1") (pintype "passive"))
    )
    (net (code "97") (name "Net-(J34-I{slash}O-Pad50)") (class "Default")
      (node (ref "J34") (pin "50") (pinfunction "I/O_50") (pintype "bidirectional"))
      (node (ref "R415") (pin "2") (pinfunction "2_2") (pintype "passive"))
    )
    (net (code "98") (name "Net-(J34-I{slash}O-Pad51)") (class "Default")
      (node (ref "J34") (pin "51") (pinfunction "I/O_51") (pintype "bidirectional"))
      (node (ref "L35") (pin "1") (pinfunction "1_1") (pintype "passive"))
    )
    (net (code "99") (name "Net-(J34-I{slash}O-Pad54)") (class "Default")
      (node (ref "J34") (pin "54") (pinfunction "I/O_54") (pintype "bidirectional"))
      (node (ref "R416") (pin "2") (pinfunction "2_2") (pintype "passive"))
    )
    (net (code "100") (name "Net-(J34-I{slash}O-Pad55)") (class "Default")
      (node (ref "J34") (pin "55") (pinfunction "I/O_55") (pintype "bidirectional"))
      (node (ref "L37") (pin "1") (pinfunction "1_1") (pintype "passive"))
    )
    (net (code "101") (name "Net-(J34-I{slash}O-Pad58)") (class "Default")
      (node (ref "J34") (pin "58") (pinfunction "I/O_58") (pintype "bidirectional"))
      (node (ref "R417") (pin "2") (pinfunction "2_2") (pintype "passive"))
    )
    (net (code "102") (name "Net-(J34-I{slash}O-Pad59)") (class "Default")
      (node (ref "J34") (pin "59") (pinfunction "I/O_59") (pintype "bidirectional"))
      (node (ref "L38") (pin "1") (pinfunction "1_1") (pintype "passive"))
    )
    (net (code "103") (name "Net-(J34-I{slash}O-Pad62)") (class "Default")
      (node (ref "J34") (pin "62") (pinfunction "I/O_62") (pintype "bidirectional"))
      (node (ref "R418") (pin "2") (pinfunction "2_2") (pintype "passive"))
    )
    (net (code "104") (name "Net-(J34-I{slash}O-Pad63)") (class "Default")
      (node (ref "J34") (pin "63") (pinfunction "I/O_63") (pintype "bidirectional"))
      (node (ref "L39") (pin "1") (pinfunction "1_1") (pintype "passive"))
    )
    (net (code "105") (name "Net-(U29-EN)") (class "Default")
      (node (ref "R346") (pin "1") (pinfunction "1_1") (pintype "passive"))
      (node (ref "U29") (pin "10") (pinfunction "EN_10") (pintype "input"))
    )
    (net (code "106") (name "Net-(U29-NC)") (class "Default")
      (node (ref "R345") (pin "2") (pinfunction "2_2") (pintype "passive"))
      (node (ref "U29") (pin "7") (pinfunction "NC_7") (pintype "passive"))
    )
    (net (code "107") (name "Net-(U30-EN)") (class "Default")
      (node (ref "R347") (pin "2") (pinfunction "2_2") (pintype "passive"))
      (node (ref "U30") (pin "10") (pinfunction "EN_10") (pintype "input"))
    )
    (net (code "108") (name "Net-(U30-NC)") (class "Default")
      (node (ref "R348") (pin "1") (pinfunction "1_1") (pintype "passive"))
      (node (ref "U30") (pin "7") (pinfunction "NC_7") (pintype "passive"))
    )
    (net (code "109") (name "Net-(U31-EN)") (class "Default")
      (node (ref "R350") (pin "1") (pinfunction "1_1") (pintype "passive"))
      (node (ref "U31") (pin "10") (pinfunction "EN_10") (pintype "input"))
    )
    (net (code "110") (name "Net-(U31-NC)") (class "Default")
      (node (ref "R349") (pin "2") (pinfunction "2_2") (pintype "passive"))
      (node (ref "U31") (pin "7") (pinfunction "NC_7") (pintype "passive"))
    )
    (net (code "111") (name "Net-(U34-EN)") (class "Default")
      (node (ref "R341") (pin "2") (pinfunction "2_2") (pintype "passive"))
      (node (ref "U34") (pin "10") (pinfunction "EN_10") (pintype "input"))
    )
    (net (code "112") (name "Net-(U34-NC)") (class "Default")
      (node (ref "R342") (pin "1") (pinfunction "1_1") (pintype "passive"))
      (node (ref "U34") (pin "7") (pinfunction "NC_7") (pintype "passive"))
    )
    (net (code "113") (name "Net-(U53-EN)") (class "Default")
      (node (ref "R344") (pin "1") (pinfunction "1_1") (pintype "passive"))
      (node (ref "U53") (pin "10") (pinfunction "EN_10") (pintype "input"))
    )
    (net (code "114") (name "Net-(U53-NC)") (class "Default")
      (node (ref "R343") (pin "2") (pinfunction "2_2") (pintype "passive"))
      (node (ref "U53") (pin "7") (pinfunction "NC_7") (pintype "passive"))
    )
    (net (code "115") (name "intG") (class "Default")
      (node (ref "C259") (pin "1") (pinfunction "1_1") (pintype "passive"))
      (node (ref "C262") (pin "1") (pinfunction "1_1") (pintype "passive"))
      (node (ref "C264") (pin "1") (pinfunction "1_1") (pintype "passive"))
      (node (ref "C266") (pin "1") (pinfunction "1_1") (pintype "passive"))
      (node (ref "C268") (pin "1") (pinfunction "1_1") (pintype "passive"))
      (node (ref "J34") (pin "12") (pinfunction "I/O_12") (pintype "bidirectional"))
      (node (ref "J34") (pin "16") (pinfunction "I/O_16") (pintype "bidirectional"))
      (node (ref "J34") (pin "20") (pinfunction "I/O_20") (pintype "bidirectional"))
      (node (ref "J34") (pin "24") (pinfunction "I/O_24") (pintype "bidirectional"))
      (node (ref "J34") (pin "28") (pinfunction "I/O_28") (pintype "bidirectional"))
      (node (ref "J34") (pin "32") (pinfunction "I/O_32") (pintype "bidirectional"))
      (node (ref "J34") (pin "36") (pinfunction "I/O_36") (pintype "bidirectional"))
      (node (ref "J34") (pin "4") (pinfunction "I/O_4") (pintype "bidirectional"))
      (node (ref "J34") (pin "40") (pinfunction "I/O_40") (pintype "bidirectional"))
      (node (ref "J34") (pin "44") (pinfunction "I/O_44") (pintype "bidirectional"))
      (node (ref "J34") (pin "48") (pinfunction "I/O_48") (pintype "bidirectional"))
      (node (ref "J34") (pin "52") (pinfunction "I/O_52") (pintype "bidirectional"))
      (node (ref "J34") (pin "56") (pinfunction "I/O_56") (pintype "bidirectional"))
      (node (ref "J34") (pin "60") (pinfunction "I/O_60") (pintype "bidirectional"))
      (node (ref "J34") (pin "64") (pinfunction "I/O_64") (pintype "bidirectional"))
      (node (ref "J34") (pin "8") (pinfunction "I/O_8") (pintype "bidirectional"))
      (node (ref "J38") (pin "2") (pinfunction "2_2") (pintype "bidirectional"))
      (node (ref "R340") (pin "2") (pinfunction "2_2") (pintype "passive"))
      (node (ref "U29") (pin "15") (pinfunction "GND2_15") (pintype "power_in"))
      (node (ref "U29") (pin "9") (pinfunction "GND2_9") (pintype "power_in"))
      (node (ref "U30") (pin "2") (pinfunction "GND1_2") (pintype "power_in"))
      (node (ref "U30") (pin "8") (pinfunction "GND1_8") (pintype "power_in"))
      (node (ref "U31") (pin "15") (pinfunction "GND2_15") (pintype "power_in"))
      (node (ref "U31") (pin "9") (pinfunction "GND2_9") (pintype "power_in"))
      (node (ref "U34") (pin "2") (pinfunction "GND1_2") (pintype "power_in"))
      (node (ref "U34") (pin "8") (pinfunction "GND1_8") (pintype "power_in"))
      (node (ref "U53") (pin "15") (pinfunction "GND2_15") (pintype "power_in"))
      (node (ref "U53") (pin "9") (pinfunction "GND2_9") (pintype "power_in"))
    )
    (net (code "116") (name "unconnected-(J34-I{slash}O-Pad1)") (class "Default")
      (node (ref "J34") (pin "1") (pinfunction "I/O_1") (pintype "bidirectional"))
    )
    (net (code "117") (name "unconnected-(J34-I{slash}O-Pad5)") (class "Default")
      (node (ref "J34") (pin "5") (pinfunction "I/O_5") (pintype "bidirectional"))
    )
    (net (code "118") (name "unconnected-(J34-I{slash}O-Pad9)") (class "Default")
      (node (ref "J34") (pin "9") (pinfunction "I/O_9") (pintype "bidirectional"))
    )
    (net (code "119") (name "unconnected-(J34-I{slash}O-Pad13)") (class "Default")
      (node (ref "J34") (pin "13") (pinfunction "I/O_13") (pintype "bidirectional"))
    )
    (net (code "120") (name "unconnected-(J34-I{slash}O-Pad17)") (class "Default")
      (node (ref "J34") (pin "17") (pinfunction "I/O_17") (pintype "bidirectional"))
    )
    (net (code "121") (name "unconnected-(J34-I{slash}O-Pad18)") (class "Default")
      (node (ref "J34") (pin "18") (pinfunction "I/O_18") (pintype "bidirectional+no_connect"))
    )
    (net (code "122") (name "unconnected-(J34-I{slash}O-Pad21)") (class "Default")
      (node (ref "J34") (pin "21") (pinfunction "I/O_21") (pintype "bidirectional"))
    )
    (net (code "123") (name "unconnected-(J34-I{slash}O-Pad25)") (class "Default")
      (node (ref "J34") (pin "25") (pinfunction "I/O_25") (pintype "bidirectional"))
    )
    (net (code "124") (name "unconnected-(J34-I{slash}O-Pad29)") (class "Default")
      (node (ref "J34") (pin "29") (pinfunction "I/O_29") (pintype "bidirectional"))
    )
    (net (code "125") (name "unconnected-(J34-I{slash}O-Pad33)") (class "Default")
      (node (ref "J34") (pin "33") (pinfunction "I/O_33") (pintype "bidirectional"))
    )
    (net (code "126") (name "unconnected-(J34-I{slash}O-Pad37)") (class "Default")
      (node (ref "J34") (pin "37") (pinfunction "I/O_37") (pintype "bidirectional"))
    )
    (net (code "127") (name "unconnected-(J34-I{slash}O-Pad41)") (class "Default")
      (node (ref "J34") (pin "41") (pinfunction "I/O_41") (pintype "bidirectional"))
    )
    (net (code "128") (name "unconnected-(J34-I{slash}O-Pad45)") (class "Default")
      (node (ref "J34") (pin "45") (pinfunction "I/O_45") (pintype "bidirectional"))
    )
    (net (code "129") (name "unconnected-(J34-I{slash}O-Pad49)") (class "Default")
      (node (ref "J34") (pin "49") (pinfunction "I/O_49") (pintype "bidirectional"))
    )
    (net (code "130") (name "unconnected-(J34-I{slash}O-Pad53)") (class "Default")
      (node (ref "J34") (pin "53") (pinfunction "I/O_53") (pintype "bidirectional"))
    )
    (net (code "131") (name "unconnected-(J34-I{slash}O-Pad57)") (class "Default")
      (node (ref "J34") (pin "57") (pinfunction "I/O_57") (pintype "bidirectional"))
    )
    (net (code "132") (name "unconnected-(J34-I{slash}O-Pad61)") (class "Default")
      (node (ref "J34") (pin "61") (pinfunction "I/O_61") (pintype "bidirectional"))
    )
    (net (code "133") (name "unconnected-(R394-Pad2)") (class "Default")
      (node (ref "R394") (pin "2") (pinfunction "2_2") (pintype "passive+no_connect"))
    )
    (net (code "134") (name "unconnected-(R395-Pad2)") (class "Default")
      (node (ref "R395") (pin "2") (pinfunction "2_2") (pintype "passive+no_connect"))
    )
    (net (code "135") (name "unconnected-(R396-Pad2)") (class "Default")
      (node (ref "R396") (pin "2") (pinfunction "2_2") (pintype "passive+no_connect"))
    )
    (net (code "136") (name "unconnected-(R398-Pad2)") (class "Default")
      (node (ref "R398") (pin "2") (pinfunction "2_2") (pintype "passive+no_connect"))
    )
    (net (code "137") (name "unconnected-(R400-Pad2)") (class "Default")
      (node (ref "R400") (pin "2") (pinfunction "2_2") (pintype "passive+no_connect"))
    )
    (net (code "138") (name "unconnected-(R412-Pad2)") (class "Default")
      (node (ref "R412") (pin "2") (pinfunction "2_2") (pintype "passive+no_connect"))
    )
    (net (code "139") (name "unconnected-(R414-Pad2)") (class "Default")
      (node (ref "R414") (pin "2") (pinfunction "2_2") (pintype "passive+no_connect"))
    )
    (net (code "140") (name "unconnected-(R435-Pad1)") (class "Default")
      (node (ref "R435") (pin "1") (pinfunction "1_1") (pintype "passive"))
    )
    (net (code "141") (name "unconnected-(R435-Pad2)") (class "Default")
      (node (ref "R435") (pin "2") (pinfunction "2_2") (pintype "passive"))
    )
  )
)
